# vent_bjt2_i2c_pwm_small.net
KiCad netlist of a schematic drawn in EAGLE
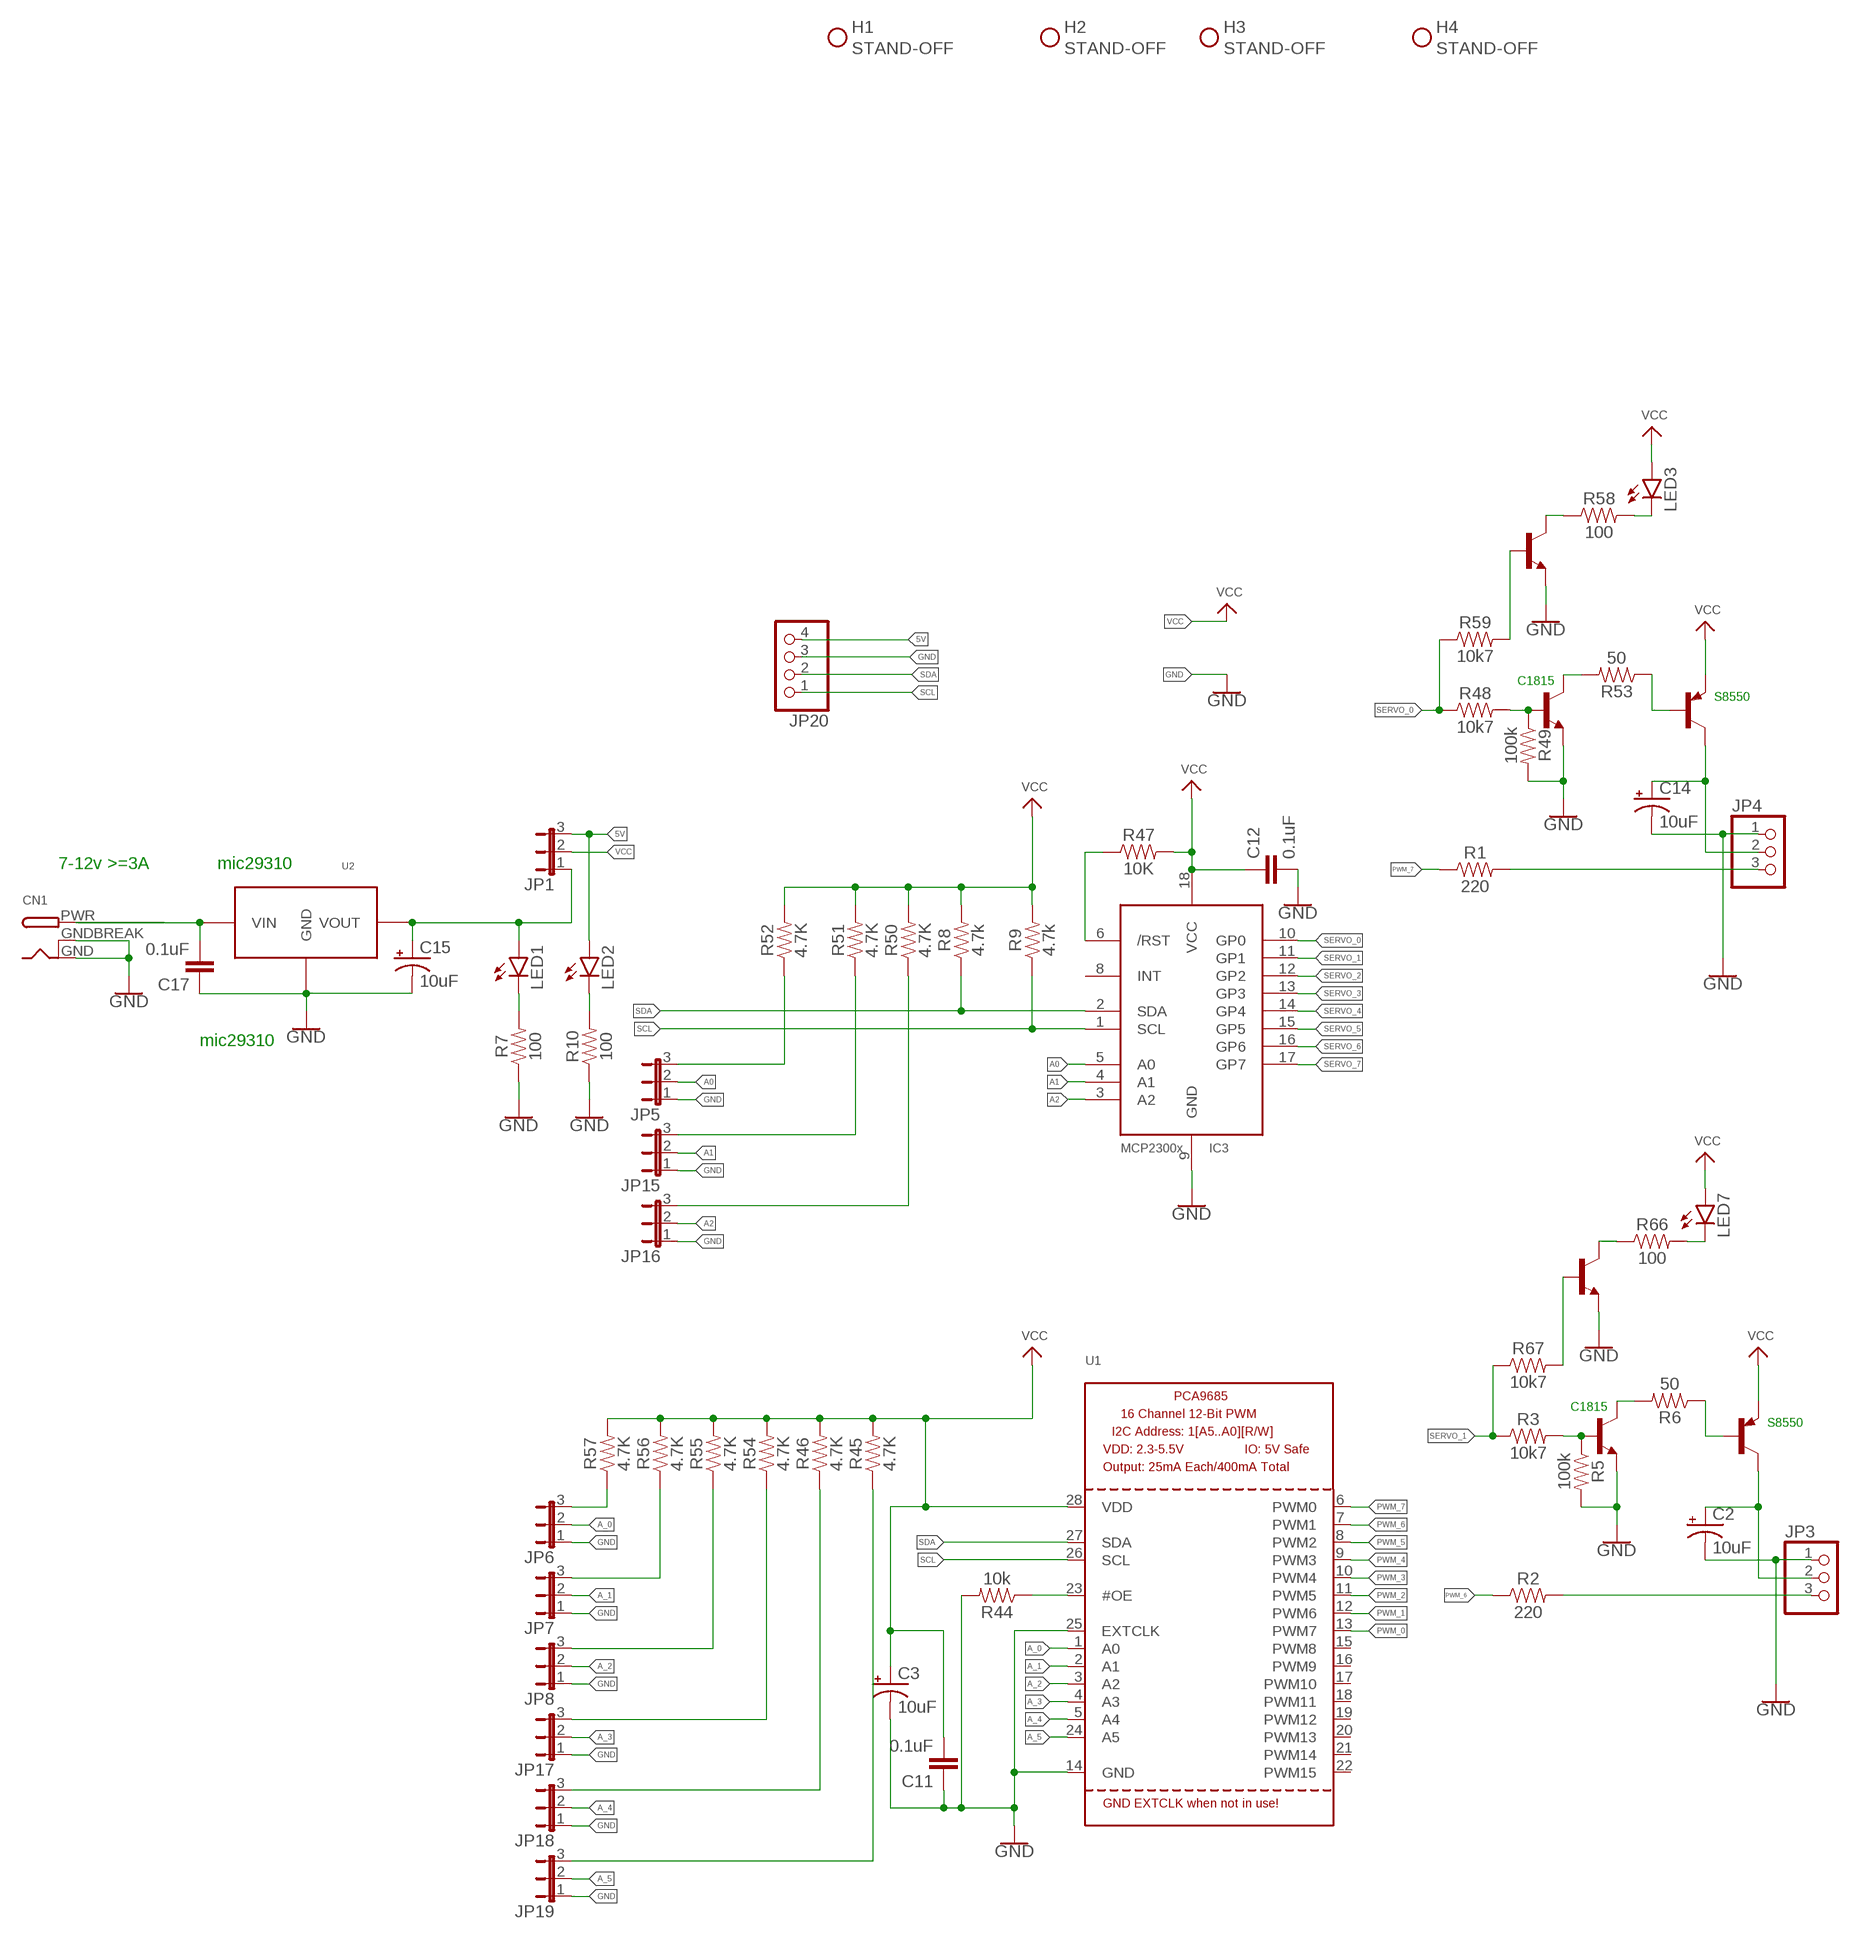
[diagram p0: schematic, sheet 1, part 1 of 2]
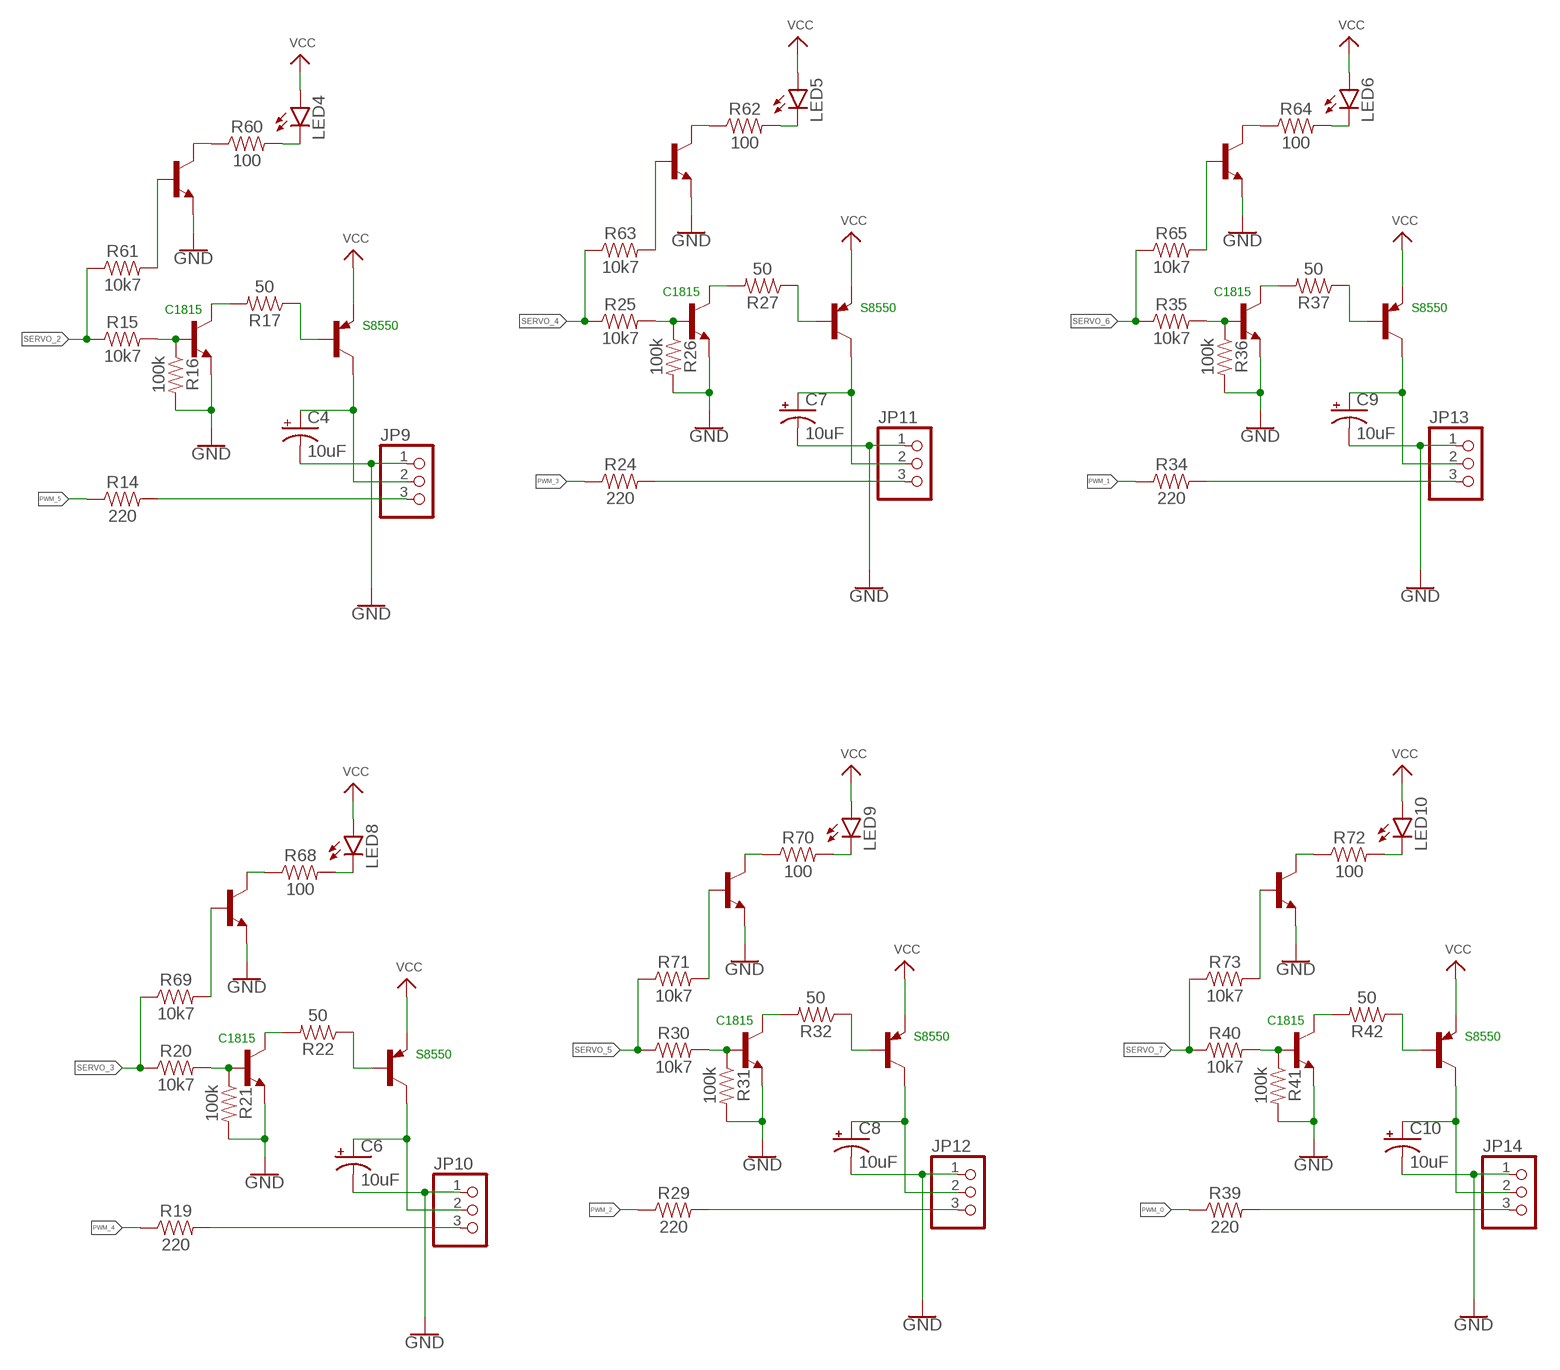
[diagram p1: schematic, sheet 1, part 2 of 2]

(export (version "E")
  (design (tool "Eeschema 10.0.6"))
  (components
    (comp (ref "C2")
      (value "10uF")
      (footprint "eagle-import:CPOL-RADIAL-2.5MM-5MM")
      (libsource (lib "eagle-import") (part "10UF-POLAR-RADIAL-2.5MM-25V-20%"))
    )
    (comp (ref "C3")
      (value "10uF")
      (footprint "eagle-import:CPOL-RADIAL-2.5MM-5MM")
      (libsource (lib "eagle-import") (part "10UF-POLAR-RADIAL-2.5MM-25V-20%"))
    )
    (comp (ref "C4")
      (value "10uF")
      (footprint "eagle-import:CPOL-RADIAL-2.5MM-5MM")
      (libsource (lib "eagle-import") (part "10UF-POLAR-RADIAL-2.5MM-25V-20%"))
    )
    (comp (ref "C6")
      (value "10uF")
      (footprint "eagle-import:CPOL-RADIAL-2.5MM-5MM")
      (libsource (lib "eagle-import") (part "10UF-POLAR-RADIAL-2.5MM-25V-20%"))
    )
    (comp (ref "C7")
      (value "10uF")
      (footprint "eagle-import:CPOL-RADIAL-2.5MM-5MM")
      (libsource (lib "eagle-import") (part "10UF-POLAR-RADIAL-2.5MM-25V-20%"))
    )
    (comp (ref "C8")
      (value "10uF")
      (footprint "eagle-import:CPOL-RADIAL-2.5MM-5MM")
      (libsource (lib "eagle-import") (part "10UF-POLAR-RADIAL-2.5MM-25V-20%"))
    )
    (comp (ref "C9")
      (value "10uF")
      (footprint "eagle-import:CPOL-RADIAL-2.5MM-5MM")
      (libsource (lib "eagle-import") (part "10UF-POLAR-RADIAL-2.5MM-25V-20%"))
    )
    (comp (ref "C10")
      (value "10uF")
      (footprint "eagle-import:CPOL-RADIAL-2.5MM-5MM")
      (libsource (lib "eagle-import") (part "10UF-POLAR-RADIAL-2.5MM-25V-20%"))
    )
    (comp (ref "C11")
      (value "0.1uF")
      (footprint "eagle-import:CAP-PTH-SMALL-KIT")
      (libsource (lib "eagle-import") (part "0.1UF-KIT-EZ-50V-20%"))
    )
    (comp (ref "C12")
      (value "0.1uF")
      (footprint "eagle-import:CAP-PTH-SMALL-KIT")
      (libsource (lib "eagle-import") (part "0.1UF-KIT-EZ-50V-20%"))
    )
    (comp (ref "C14")
      (value "10uF")
      (footprint "eagle-import:CPOL-RADIAL-2.5MM-5MM")
      (libsource (lib "eagle-import") (part "10UF-POLAR-RADIAL-2.5MM-25V-20%"))
    )
    (comp (ref "C15")
      (value "10uF")
      (footprint "eagle-import:CPOL-RADIAL-2.5MM-5MM")
      (libsource (lib "eagle-import") (part "10UF-POLAR-RADIAL-2.5MM-25V-20%"))
    )
    (comp (ref "C17")
      (value "0.1uF")
      (footprint "eagle-import:CAP-PTH-SMALL-KIT")
      (libsource (lib "eagle-import") (part "0.1UF-KIT-EZ-50V-20%"))
    )
    (comp (ref "CN1")
      (value "DCBARRELPTH")
      (footprint "eagle-import:DCJACK_2MM_PTH")
      (libsource (lib "eagle-import") (part "DCBARRELPTH"))
    )
    (comp (ref "H1")
      (value "STAND-OFF")
      (footprint "eagle-import:STAND-OFF")
      (libsource (lib "eagle-import") (part "STAND-OFF"))
    )
    (comp (ref "H2")
      (value "STAND-OFF")
      (footprint "eagle-import:STAND-OFF")
      (libsource (lib "eagle-import") (part "STAND-OFF"))
    )
    (comp (ref "H3")
      (value "STAND-OFF")
      (footprint "eagle-import:STAND-OFF")
      (libsource (lib "eagle-import") (part "STAND-OFF"))
    )
    (comp (ref "H4")
      (value "STAND-OFF")
      (footprint "eagle-import:STAND-OFF")
      (libsource (lib "eagle-import") (part "STAND-OFF"))
    )
    (comp (ref "IC3")
      (value "MCP23008/P")
      (footprint "eagle-import:DIL18")
      (libsource (lib "eagle-import") (part "MCP23008/P"))
    )
    (comp (ref "JP1")
      (value "JP2E")
      (footprint "eagle-import:JP2")
      (libsource (lib "eagle-import") (part "JP2E"))
    )
    (comp (ref "JP3")
      (value "PINHD-1X3")
      (footprint "eagle-import:1X03")
      (libsource (lib "eagle-import") (part "PINHD-1X3"))
    )
    (comp (ref "JP4")
      (value "PINHD-1X3")
      (footprint "eagle-import:1X03")
      (libsource (lib "eagle-import") (part "PINHD-1X3"))
    )
    (comp (ref "JP5")
      (value "JP2E")
      (footprint "eagle-import:JP2")
      (libsource (lib "eagle-import") (part "JP2E"))
    )
    (comp (ref "JP6")
      (value "JP2E")
      (footprint "eagle-import:JP2")
      (libsource (lib "eagle-import") (part "JP2E"))
    )
    (comp (ref "JP7")
      (value "JP2E")
      (footprint "eagle-import:JP2")
      (libsource (lib "eagle-import") (part "JP2E"))
    )
    (comp (ref "JP8")
      (value "JP2E")
      (footprint "eagle-import:JP2")
      (libsource (lib "eagle-import") (part "JP2E"))
    )
    (comp (ref "JP9")
      (value "PINHD-1X3")
      (footprint "eagle-import:1X03")
      (libsource (lib "eagle-import") (part "PINHD-1X3"))
    )
    (comp (ref "JP10")
      (value "PINHD-1X3")
      (footprint "eagle-import:1X03")
      (libsource (lib "eagle-import") (part "PINHD-1X3"))
    )
    (comp (ref "JP11")
      (value "PINHD-1X3")
      (footprint "eagle-import:1X03")
      (libsource (lib "eagle-import") (part "PINHD-1X3"))
    )
    (comp (ref "JP12")
      (value "PINHD-1X3")
      (footprint "eagle-import:1X03")
      (libsource (lib "eagle-import") (part "PINHD-1X3"))
    )
    (comp (ref "JP13")
      (value "PINHD-1X3")
      (footprint "eagle-import:1X03")
      (libsource (lib "eagle-import") (part "PINHD-1X3"))
    )
    (comp (ref "JP14")
      (value "PINHD-1X3")
      (footprint "eagle-import:1X03")
      (libsource (lib "eagle-import") (part "PINHD-1X3"))
    )
    (comp (ref "JP15")
      (value "JP2E")
      (footprint "eagle-import:JP2")
      (libsource (lib "eagle-import") (part "JP2E"))
    )
    (comp (ref "JP16")
      (value "JP2E")
      (footprint "eagle-import:JP2")
      (libsource (lib "eagle-import") (part "JP2E"))
    )
    (comp (ref "JP17")
      (value "JP2E")
      (footprint "eagle-import:JP2")
      (libsource (lib "eagle-import") (part "JP2E"))
    )
    (comp (ref "JP18")
      (value "JP2E")
      (footprint "eagle-import:JP2")
      (libsource (lib "eagle-import") (part "JP2E"))
    )
    (comp (ref "JP19")
      (value "JP2E")
      (footprint "eagle-import:JP2")
      (libsource (lib "eagle-import") (part "JP2E"))
    )
    (comp (ref "JP20")
      (value "PINHD-1X4")
      (footprint "eagle-import:1X04")
      (libsource (lib "eagle-import") (part "PINHD-1X4"))
    )
    (comp (ref "LED1")
      (value "LEDCHIPLED_1206")
      (footprint "eagle-import:CHIPLED_1206")
      (libsource (lib "eagle-import") (part "LEDCHIPLED_1206"))
    )
    (comp (ref "LED2")
      (value "LEDCHIPLED_1206")
      (footprint "eagle-import:CHIPLED_1206")
      (libsource (lib "eagle-import") (part "LEDCHIPLED_1206"))
    )
    (comp (ref "LED3")
      (value "LEDCHIPLED_1206")
      (footprint "eagle-import:CHIPLED_1206")
      (libsource (lib "eagle-import") (part "LEDCHIPLED_1206"))
    )
    (comp (ref "LED4")
      (value "LEDCHIPLED_1206")
      (footprint "eagle-import:CHIPLED_1206")
      (libsource (lib "eagle-import") (part "LEDCHIPLED_1206"))
    )
    (comp (ref "LED5")
      (value "LEDCHIPLED_1206")
      (footprint "eagle-import:CHIPLED_1206")
      (libsource (lib "eagle-import") (part "LEDCHIPLED_1206"))
    )
    (comp (ref "LED6")
      (value "LEDCHIPLED_1206")
      (footprint "eagle-import:CHIPLED_1206")
      (libsource (lib "eagle-import") (part "LEDCHIPLED_1206"))
    )
    (comp (ref "LED7")
      (value "LEDCHIPLED_1206")
      (footprint "eagle-import:CHIPLED_1206")
      (libsource (lib "eagle-import") (part "LEDCHIPLED_1206"))
    )
    (comp (ref "LED8")
      (value "LEDCHIPLED_1206")
      (footprint "eagle-import:CHIPLED_1206")
      (libsource (lib "eagle-import") (part "LEDCHIPLED_1206"))
    )
    (comp (ref "LED9")
      (value "LEDCHIPLED_1206")
      (footprint "eagle-import:CHIPLED_1206")
      (libsource (lib "eagle-import") (part "LEDCHIPLED_1206"))
    )
    (comp (ref "LED10")
      (value "LEDCHIPLED_1206")
      (footprint "eagle-import:CHIPLED_1206")
      (libsource (lib "eagle-import") (part "LEDCHIPLED_1206"))
    )
    (comp (ref "Q1")
      (value "2N2907")
      (footprint "eagle-import:TO92-EBC-OVAL")
      (libsource (lib "eagle-import") (part "2N2907"))
    )
    (comp (ref "Q2")
      (value "2N2907")
      (footprint "eagle-import:TO92-EBC-OVAL")
      (libsource (lib "eagle-import") (part "2N2907"))
    )
    (comp (ref "Q3")
      (value "2N2907")
      (footprint "eagle-import:TO92-EBC-OVAL")
      (libsource (lib "eagle-import") (part "2N2907"))
    )
    (comp (ref "Q4")
      (value "2N2907")
      (footprint "eagle-import:TO92-EBC-OVAL")
      (libsource (lib "eagle-import") (part "2N2907"))
    )
    (comp (ref "Q5")
      (value "2N2907")
      (footprint "eagle-import:TO92-EBC-OVAL")
      (libsource (lib "eagle-import") (part "2N2907"))
    )
    (comp (ref "Q6")
      (value "2N2907")
      (footprint "eagle-import:TO92-EBC-OVAL")
      (libsource (lib "eagle-import") (part "2N2907"))
    )
    (comp (ref "Q7")
      (value "2N2907")
      (footprint "eagle-import:TO92-EBC-OVAL")
      (libsource (lib "eagle-import") (part "2N2907"))
    )
    (comp (ref "Q9")
      (value "2N2907")
      (footprint "eagle-import:TO92-EBC-OVAL")
      (libsource (lib "eagle-import") (part "2N2907"))
    )
    (comp (ref "R1")
      (value "220")
      (footprint "eagle-import:AXIAL-0.3")
      (libsource (lib "eagle-import") (part "10KOHM-HORIZ-1/4W-1%"))
    )
    (comp (ref "R2")
      (value "220")
      (footprint "eagle-import:AXIAL-0.3")
      (libsource (lib "eagle-import") (part "10KOHM-HORIZ-1/4W-1%"))
    )
    (comp (ref "R3")
      (value "10k7")
      (footprint "eagle-import:AXIAL-0.3")
      (libsource (lib "eagle-import") (part "10KOHM-HORIZ-1/4W-1%"))
    )
    (comp (ref "R5")
      (value "100k")
      (footprint "eagle-import:AXIAL-0.3")
      (libsource (lib "eagle-import") (part "10KOHM-HORIZ-1/4W-1%"))
    )
    (comp (ref "R6")
      (value "50")
      (footprint "eagle-import:AXIAL-0.3")
      (libsource (lib "eagle-import") (part "10KOHM-HORIZ-1/4W-1%"))
    )
    (comp (ref "R7")
      (value "100")
      (footprint "eagle-import:AXIAL-0.3")
      (libsource (lib "eagle-import") (part "10KOHM-HORIZ-1/4W-1%"))
    )
    (comp (ref "R8")
      (value "4.7k")
      (footprint "eagle-import:AXIAL-0.3")
      (libsource (lib "eagle-import") (part "10KOHM-HORIZ-1/4W-1%"))
    )
    (comp (ref "R9")
      (value "4.7k")
      (footprint "eagle-import:AXIAL-0.3")
      (libsource (lib "eagle-import") (part "10KOHM-HORIZ-1/4W-1%"))
    )
    (comp (ref "R10")
      (value "100")
      (footprint "eagle-import:AXIAL-0.3")
      (libsource (lib "eagle-import") (part "10KOHM-HORIZ-1/4W-1%"))
    )
    (comp (ref "R14")
      (value "220")
      (footprint "eagle-import:AXIAL-0.3")
      (libsource (lib "eagle-import") (part "10KOHM-HORIZ-1/4W-1%"))
    )
    (comp (ref "R15")
      (value "10k7")
      (footprint "eagle-import:AXIAL-0.3")
      (libsource (lib "eagle-import") (part "10KOHM-HORIZ-1/4W-1%"))
    )
    (comp (ref "R16")
      (value "100k")
      (footprint "eagle-import:AXIAL-0.3")
      (libsource (lib "eagle-import") (part "10KOHM-HORIZ-1/4W-1%"))
    )
    (comp (ref "R17")
      (value "50")
      (footprint "eagle-import:AXIAL-0.3")
      (libsource (lib "eagle-import") (part "10KOHM-HORIZ-1/4W-1%"))
    )
    (comp (ref "R19")
      (value "220")
      (footprint "eagle-import:AXIAL-0.3")
      (libsource (lib "eagle-import") (part "10KOHM-HORIZ-1/4W-1%"))
    )
    (comp (ref "R20")
      (value "10k7")
      (footprint "eagle-import:AXIAL-0.3")
      (libsource (lib "eagle-import") (part "10KOHM-HORIZ-1/4W-1%"))
    )
    (comp (ref "R21")
      (value "100k")
      (footprint "eagle-import:AXIAL-0.3")
      (libsource (lib "eagle-import") (part "10KOHM-HORIZ-1/4W-1%"))
    )
    (comp (ref "R22")
      (value "50")
      (footprint "eagle-import:AXIAL-0.3")
      (libsource (lib "eagle-import") (part "10KOHM-HORIZ-1/4W-1%"))
    )
    (comp (ref "R24")
      (value "220")
      (footprint "eagle-import:AXIAL-0.3")
      (libsource (lib "eagle-import") (part "10KOHM-HORIZ-1/4W-1%"))
    )
    (comp (ref "R25")
      (value "10k7")
      (footprint "eagle-import:AXIAL-0.3")
      (libsource (lib "eagle-import") (part "10KOHM-HORIZ-1/4W-1%"))
    )
    (comp (ref "R26")
      (value "100k")
      (footprint "eagle-import:AXIAL-0.3")
      (libsource (lib "eagle-import") (part "10KOHM-HORIZ-1/4W-1%"))
    )
    (comp (ref "R27")
      (value "50")
      (footprint "eagle-import:AXIAL-0.3")
      (libsource (lib "eagle-import") (part "10KOHM-HORIZ-1/4W-1%"))
    )
    (comp (ref "R29")
      (value "220")
      (footprint "eagle-import:AXIAL-0.3")
      (libsource (lib "eagle-import") (part "10KOHM-HORIZ-1/4W-1%"))
    )
    (comp (ref "R30")
      (value "10k7")
      (footprint "eagle-import:AXIAL-0.3")
      (libsource (lib "eagle-import") (part "10KOHM-HORIZ-1/4W-1%"))
    )
    (comp (ref "R31")
      (value "100k")
      (footprint "eagle-import:AXIAL-0.3")
      (libsource (lib "eagle-import") (part "10KOHM-HORIZ-1/4W-1%"))
    )
    (comp (ref "R32")
      (value "50")
      (footprint "eagle-import:AXIAL-0.3")
      (libsource (lib "eagle-import") (part "10KOHM-HORIZ-1/4W-1%"))
    )
    (comp (ref "R34")
      (value "220")
      (footprint "eagle-import:AXIAL-0.3")
      (libsource (lib "eagle-import") (part "10KOHM-HORIZ-1/4W-1%"))
    )
    (comp (ref "R35")
      (value "10k7")
      (footprint "eagle-import:AXIAL-0.3")
      (libsource (lib "eagle-import") (part "10KOHM-HORIZ-1/4W-1%"))
    )
    (comp (ref "R36")
      (value "100k")
      (footprint "eagle-import:AXIAL-0.3")
      (libsource (lib "eagle-import") (part "10KOHM-HORIZ-1/4W-1%"))
    )
    (comp (ref "R37")
      (value "50")
      (footprint "eagle-import:AXIAL-0.3")
      (libsource (lib "eagle-import") (part "10KOHM-HORIZ-1/4W-1%"))
    )
    (comp (ref "R39")
      (value "220")
      (footprint "eagle-import:AXIAL-0.3")
      (libsource (lib "eagle-import") (part "10KOHM-HORIZ-1/4W-1%"))
    )
    (comp (ref "R40")
      (value "10k7")
      (footprint "eagle-import:AXIAL-0.3")
      (libsource (lib "eagle-import") (part "10KOHM-HORIZ-1/4W-1%"))
    )
    (comp (ref "R41")
      (value "100k")
      (footprint "eagle-import:AXIAL-0.3")
      (libsource (lib "eagle-import") (part "10KOHM-HORIZ-1/4W-1%"))
    )
    (comp (ref "R42")
      (value "50")
      (footprint "eagle-import:AXIAL-0.3")
      (libsource (lib "eagle-import") (part "10KOHM-HORIZ-1/4W-1%"))
    )
    (comp (ref "R44")
      (value "10k")
      (footprint "eagle-import:AXIAL-0.3")
      (libsource (lib "eagle-import") (part "10KOHM-HORIZ-1/4W-1%"))
    )
    (comp (ref "R45")
      (value "4.7K")
      (footprint "eagle-import:AXIAL-0.3")
      (libsource (lib "eagle-import") (part "10KOHM-HORIZ-1/4W-1%"))
    )
    (comp (ref "R46")
      (value "4.7K")
      (footprint "eagle-import:AXIAL-0.3")
      (libsource (lib "eagle-import") (part "10KOHM-HORIZ-1/4W-1%"))
    )
    (comp (ref "R47")
      (value "10K")
      (footprint "eagle-import:AXIAL-0.3")
      (libsource (lib "eagle-import") (part "10KOHM-HORIZ-1/4W-1%"))
    )
    (comp (ref "R48")
      (value "10k7")
      (footprint "eagle-import:AXIAL-0.3")
      (libsource (lib "eagle-import") (part "10KOHM-HORIZ-1/4W-1%"))
    )
    (comp (ref "R49")
      (value "100k")
      (footprint "eagle-import:AXIAL-0.3")
      (libsource (lib "eagle-import") (part "10KOHM-HORIZ-1/4W-1%"))
    )
    (comp (ref "R50")
      (value "4.7K")
      (footprint "eagle-import:AXIAL-0.3")
      (libsource (lib "eagle-import") (part "10KOHM-HORIZ-1/4W-1%"))
    )
    (comp (ref "R51")
      (value "4.7K")
      (footprint "eagle-import:AXIAL-0.3")
      (libsource (lib "eagle-import") (part "10KOHM-HORIZ-1/4W-1%"))
    )
    (comp (ref "R52")
      (value "4.7K")
      (footprint "eagle-import:AXIAL-0.3")
      (libsource (lib "eagle-import") (part "10KOHM-HORIZ-1/4W-1%"))
    )
    (comp (ref "R53")
      (value "50")
      (footprint "eagle-import:AXIAL-0.3")
      (libsource (lib "eagle-import") (part "10KOHM-HORIZ-1/4W-1%"))
    )
    (comp (ref "R54")
      (value "4.7K")
      (footprint "eagle-import:AXIAL-0.3")
      (libsource (lib "eagle-import") (part "10KOHM-HORIZ-1/4W-1%"))
    )
    (comp (ref "R55")
      (value "4.7K")
      (footprint "eagle-import:AXIAL-0.3")
      (libsource (lib "eagle-import") (part "10KOHM-HORIZ-1/4W-1%"))
    )
    (comp (ref "R56")
      (value "4.7K")
      (footprint "eagle-import:AXIAL-0.3")
      (libsource (lib "eagle-import") (part "10KOHM-HORIZ-1/4W-1%"))
    )
    (comp (ref "R57")
      (value "4.7K")
      (footprint "eagle-import:AXIAL-0.3")
      (libsource (lib "eagle-import") (part "10KOHM-HORIZ-1/4W-1%"))
    )
    (comp (ref "R58")
      (value "100")
      (footprint "eagle-import:AXIAL-0.3")
      (libsource (lib "eagle-import") (part "10KOHM-HORIZ-1/4W-1%"))
    )
    (comp (ref "R59")
      (value "10k7")
      (footprint "eagle-import:AXIAL-0.3")
      (libsource (lib "eagle-import") (part "10KOHM-HORIZ-1/4W-1%"))
    )
    (comp (ref "R60")
      (value "100")
      (footprint "eagle-import:AXIAL-0.3")
      (libsource (lib "eagle-import") (part "10KOHM-HORIZ-1/4W-1%"))
    )
    (comp (ref "R61")
      (value "10k7")
      (footprint "eagle-import:AXIAL-0.3")
      (libsource (lib "eagle-import") (part "10KOHM-HORIZ-1/4W-1%"))
    )
    (comp (ref "R62")
      (value "100")
      (footprint "eagle-import:AXIAL-0.3")
      (libsource (lib "eagle-import") (part "10KOHM-HORIZ-1/4W-1%"))
    )
    (comp (ref "R63")
      (value "10k7")
      (footprint "eagle-import:AXIAL-0.3")
      (libsource (lib "eagle-import") (part "10KOHM-HORIZ-1/4W-1%"))
    )
    (comp (ref "R64")
      (value "100")
      (footprint "eagle-import:AXIAL-0.3")
      (libsource (lib "eagle-import") (part "10KOHM-HORIZ-1/4W-1%"))
    )
    (comp (ref "R65")
      (value "10k7")
      (footprint "eagle-import:AXIAL-0.3")
      (libsource (lib "eagle-import") (part "10KOHM-HORIZ-1/4W-1%"))
    )
    (comp (ref "R66")
      (value "100")
      (footprint "eagle-import:AXIAL-0.3")
      (libsource (lib "eagle-import") (part "10KOHM-HORIZ-1/4W-1%"))
    )
    (comp (ref "R67")
      (value "10k7")
      (footprint "eagle-import:AXIAL-0.3")
      (libsource (lib "eagle-import") (part "10KOHM-HORIZ-1/4W-1%"))
    )
    (comp (ref "R68")
      (value "100")
      (footprint "eagle-import:AXIAL-0.3")
      (libsource (lib "eagle-import") (part "10KOHM-HORIZ-1/4W-1%"))
    )
    (comp (ref "R69")
      (value "10k7")
      (footprint "eagle-import:AXIAL-0.3")
      (libsource (lib "eagle-import") (part "10KOHM-HORIZ-1/4W-1%"))
    )
    (comp (ref "R70")
      (value "100")
      (footprint "eagle-import:AXIAL-0.3")
      (libsource (lib "eagle-import") (part "10KOHM-HORIZ-1/4W-1%"))
    )
    (comp (ref "R71")
      (value "10k7")
      (footprint "eagle-import:AXIAL-0.3")
      (libsource (lib "eagle-import") (part "10KOHM-HORIZ-1/4W-1%"))
    )
    (comp (ref "R72")
      (value "100")
      (footprint "eagle-import:AXIAL-0.3")
      (libsource (lib "eagle-import") (part "10KOHM-HORIZ-1/4W-1%"))
    )
    (comp (ref "R73")
      (value "10k7")
      (footprint "eagle-import:AXIAL-0.3")
      (libsource (lib "eagle-import") (part "10KOHM-HORIZ-1/4W-1%"))
    )
    (comp (ref "T1")
      (value "2SC1815")
      (footprint "eagle-import:TO92-ECB")
      (libsource (lib "eagle-import") (part "2SC1815"))
    )
    (comp (ref "T2")
      (value "2SC1815")
      (footprint "eagle-import:TO92-ECB")
      (libsource (lib "eagle-import") (part "2SC1815"))
    )
    (comp (ref "T3")
      (value "2SC1815")
      (footprint "eagle-import:TO92-ECB")
      (libsource (lib "eagle-import") (part "2SC1815"))
    )
    (comp (ref "T4")
      (value "2SC1815")
      (footprint "eagle-import:TO92-ECB")
      (libsource (lib "eagle-import") (part "2SC1815"))
    )
    (comp (ref "T5")
      (value "2SC1815")
      (footprint "eagle-import:TO92-ECB")
      (libsource (lib "eagle-import") (part "2SC1815"))
    )
    (comp (ref "T6")
      (value "2SC1815")
      (footprint "eagle-import:TO92-ECB")
      (libsource (lib "eagle-import") (part "2SC1815"))
    )
    (comp (ref "T7")
      (value "2SC1815")
      (footprint "eagle-import:TO92-ECB")
      (libsource (lib "eagle-import") (part "2SC1815"))
    )
    (comp (ref "T9")
      (value "2SC1815")
      (footprint "eagle-import:TO92-ECB")
      (libsource (lib "eagle-import") (part "2SC1815"))
    )
    (comp (ref "U1")
      (value "PCA9685")
      (footprint "eagle-import:TSSOP28")
      (libsource (lib "eagle-import") (part "PCA9685"))
    )
    (comp (ref "U2")
      (value "MIC29310_TO-263")
      (footprint "eagle-import:TO263-3")
      (libsource (lib "eagle-import") (part "MIC29310_TO-263"))
    )
    (comp (ref "U3")
      (value "S9018")
      (footprint "eagle-import:TO92-EBC")
      (libsource (lib "eagle-import") (part "S9018"))
    )
    (comp (ref "U4")
      (value "S9018")
      (footprint "eagle-import:TO92-EBC")
      (libsource (lib "eagle-import") (part "S9018"))
    )
    (comp (ref "U5")
      (value "S9018")
      (footprint "eagle-import:TO92-EBC")
      (libsource (lib "eagle-import") (part "S9018"))
    )
    (comp (ref "U6")
      (value "S9018")
      (footprint "eagle-import:TO92-EBC")
      (libsource (lib "eagle-import") (part "S9018"))
    )
    (comp (ref "U7")
      (value "S9018")
      (footprint "eagle-import:TO92-EBC")
      (libsource (lib "eagle-import") (part "S9018"))
    )
    (comp (ref "U8")
      (value "S9018")
      (footprint "eagle-import:TO92-EBC")
      (libsource (lib "eagle-import") (part "S9018"))
    )
    (comp (ref "U9")
      (value "S9018")
      (footprint "eagle-import:TO92-EBC")
      (libsource (lib "eagle-import") (part "S9018"))
    )
    (comp (ref "U10")
      (value "S9018")
      (footprint "eagle-import:TO92-EBC")
      (libsource (lib "eagle-import") (part "S9018"))
    )
  )
  (nets
    (net (code "1") (name "5V") (class "Default")
      (node (ref "JP1") (pin "3") (pinfunction "3_3") (pintype "passive"))
      (node (ref "JP20") (pin "4") (pinfunction "4_4") (pintype "passive"))
      (node (ref "LED2") (pin "A") (pinfunction "A_A") (pintype "passive"))
    )
    (net (code "2") (name "A0") (class "Default")
      (node (ref "IC3") (pin "5") (pinfunction "A0_5") (pintype "input"))
      (node (ref "JP5") (pin "2") (pinfunction "2_2") (pintype "passive"))
    )
    (net (code "3") (name "A1") (class "Default")
      (node (ref "IC3") (pin "4") (pinfunction "A1_4") (pintype "input"))
      (node (ref "JP15") (pin "2") (pinfunction "2_2") (pintype "passive"))
    )
    (net (code "4") (name "A2") (class "Default")
      (node (ref "IC3") (pin "3") (pinfunction "A2_3") (pintype "input"))
      (node (ref "JP16") (pin "2") (pinfunction "2_2") (pintype "passive"))
    )
    (net (code "5") (name "A_0") (class "Default")
      (node (ref "JP6") (pin "2") (pinfunction "2_2") (pintype "passive"))
      (node (ref "U1") (pin "1") (pinfunction "A0_1") (pintype "bidirectional"))
    )
    (net (code "6") (name "A_1") (class "Default")
      (node (ref "JP7") (pin "2") (pinfunction "2_2") (pintype "passive"))
      (node (ref "U1") (pin "2") (pinfunction "A1_2") (pintype "bidirectional"))
    )
    (net (code "7") (name "A_2") (class "Default")
      (node (ref "JP8") (pin "2") (pinfunction "2_2") (pintype "passive"))
      (node (ref "U1") (pin "3") (pinfunction "A2_3") (pintype "bidirectional"))
    )
    (net (code "8") (name "A_3") (class "Default")
      (node (ref "JP17") (pin "2") (pinfunction "2_2") (pintype "passive"))
      (node (ref "U1") (pin "4") (pinfunction "A3_4") (pintype "bidirectional"))
    )
    (net (code "9") (name "A_4") (class "Default")
      (node (ref "JP18") (pin "2") (pinfunction "2_2") (pintype "passive"))
      (node (ref "U1") (pin "5") (pinfunction "A4_5") (pintype "bidirectional"))
    )
    (net (code "10") (name "A_5") (class "Default")
      (node (ref "JP19") (pin "2") (pinfunction "2_2") (pintype "passive"))
      (node (ref "U1") (pin "24") (pinfunction "A5_24") (pintype "bidirectional"))
    )
    (net (code "11") (name "GND") (class "Default")
      (node (ref "C10") (pin "2") (pinfunction "-_2") (pintype "passive"))
      (node (ref "C11") (pin "1") (pinfunction "1_1") (pintype "passive"))
      (node (ref "C12") (pin "2") (pinfunction "2_2") (pintype "passive"))
      (node (ref "C14") (pin "2") (pinfunction "-_2") (pintype "passive"))
      (node (ref "C15") (pin "2") (pinfunction "-_2") (pintype "passive"))
      (node (ref "C17") (pin "1") (pinfunction "1_1") (pintype "passive"))
      (node (ref "C2") (pin "2") (pinfunction "-_2") (pintype "passive"))
      (node (ref "C3") (pin "2") (pinfunction "-_2") (pintype "passive"))
      (node (ref "C4") (pin "2") (pinfunction "-_2") (pintype "passive"))
      (node (ref "C6") (pin "2") (pinfunction "-_2") (pintype "passive"))
      (node (ref "C7") (pin "2") (pinfunction "-_2") (pintype "passive"))
      (node (ref "C8") (pin "2") (pinfunction "-_2") (pintype "passive"))
      (node (ref "C9") (pin "2") (pinfunction "-_2") (pintype "passive"))
      (node (ref "CN1") (pin "GND") (pinfunction "GND_GND") (pintype "power_in"))
      (node (ref "CN1") (pin "GNDBREAK") (pinfunction "GNDBREAK_GNDBREAK") (pintype "power_in"))
      (node (ref "IC3") (pin "9") (pinfunction "GND_9") (pintype "power_in"))
      (node (ref "JP10") (pin "1") (pinfunction "1_1") (pintype "passive"))
      (node (ref "JP11") (pin "1") (pinfunction "1_1") (pintype "passive"))
      (node (ref "JP12") (pin "1") (pinfunction "1_1") (pintype "passive"))
      (node (ref "JP13") (pin "1") (pinfunction "1_1") (pintype "passive"))
      (node (ref "JP14") (pin "1") (pinfunction "1_1") (pintype "passive"))
      (node (ref "JP15") (pin "1") (pinfunction "1_1") (pintype "passive"))
      (node (ref "JP16") (pin "1") (pinfunction "1_1") (pintype "passive"))
      (node (ref "JP17") (pin "1") (pinfunction "1_1") (pintype "passive"))
      (node (ref "JP18") (pin "1") (pinfunction "1_1") (pintype "passive"))
      (node (ref "JP19") (pin "1") (pinfunction "1_1") (pintype "passive"))
      (node (ref "JP20") (pin "3") (pinfunction "3_3") (pintype "passive"))
      (node (ref "JP3") (pin "1") (pinfunction "1_1") (pintype "passive"))
      (node (ref "JP4") (pin "1") (pinfunction "1_1") (pintype "passive"))
      (node (ref "JP5") (pin "1") (pinfunction "1_1") (pintype "passive"))
      (node (ref "JP6") (pin "1") (pinfunction "1_1") (pintype "passive"))
      (node (ref "JP7") (pin "1") (pinfunction "1_1") (pintype "passive"))
      (node (ref "JP8") (pin "1") (pinfunction "1_1") (pintype "passive"))
      (node (ref "JP9") (pin "1") (pinfunction "1_1") (pintype "passive"))
      (node (ref "R10") (pin "P$1") (pinfunction "1_P$1") (pintype "passive"))
      (node (ref "R16") (pin "P$2") (pinfunction "2_P$2") (pintype "passive"))
      (node (ref "R21") (pin "P$2") (pinfunction "2_P$2") (pintype "passive"))
      (node (ref "R26") (pin "P$2") (pinfunction "2_P$2") (pintype "passive"))
      (node (ref "R31") (pin "P$2") (pinfunction "2_P$2") (pintype "passive"))
      (node (ref "R36") (pin "P$2") (pinfunction "2_P$2") (pintype "passive"))
      (node (ref "R41") (pin "P$2") (pinfunction "2_P$2") (pintype "passive"))
      (node (ref "R44") (pin "P$2") (pinfunction "2_P$2") (pintype "passive"))
      (node (ref "R49") (pin "P$2") (pinfunction "2_P$2") (pintype "passive"))
      (node (ref "R5") (pin "P$2") (pinfunction "2_P$2") (pintype "passive"))
      (node (ref "R7") (pin "P$1") (pinfunction "1_P$1") (pintype "passive"))
      (node (ref "T1") (pin "E") (pinfunction "E_E") (pintype "passive"))
      (node (ref "T2") (pin "E") (pinfunction "E_E") (pintype "passive"))
      (node (ref "T3") (pin "E") (pinfunction "E_E") (pintype "passive"))
      (node (ref "T4") (pin "E") (pinfunction "E_E") (pintype "passive"))
      (node (ref "T5") (pin "E") (pinfunction "E_E") (pintype "passive"))
      (node (ref "T6") (pin "E") (pinfunction "E_E") (pintype "passive"))
      (node (ref "T7") (pin "E") (pinfunction "E_E") (pintype "passive"))
      (node (ref "T9") (pin "E") (pinfunction "E_E") (pintype "passive"))
      (node (ref "U1") (pin "14") (pinfunction "GND_14") (pintype "power_in"))
      (node (ref "U1") (pin "25") (pinfunction "EXTCLK_25") (pintype "input"))
      (node (ref "U10") (pin "E") (pinfunction "E_E") (pintype "passive"))
      (node (ref "U2") (pin "2") (pinfunction "GND_2") (pintype "power_in"))
      (node (ref "U2") (pin "TAB") (pinfunction "GND_TAB") (pintype "power_in"))
      (node (ref "U3") (pin "E") (pinfunction "E_E") (pintype "passive"))
      (node (ref "U4") (pin "E") (pinfunction "E_E") (pintype "passive"))
      (node (ref "U5") (pin "E") (pinfunction "E_E") (pintype "passive"))
      (node (ref "U6") (pin "E") (pinfunction "E_E") (pintype "passive"))
      (node (ref "U7") (pin "E") (pinfunction "E_E") (pintype "passive"))
      (node (ref "U8") (pin "E") (pinfunction "E_E") (pintype "passive"))
      (node (ref "U9") (pin "E") (pinfunction "E_E") (pintype "passive"))
    )
    (net (code "12") (name "Net-(C2-+)") (class "Default")
      (node (ref "C2") (pin "1") (pinfunction "+_1") (pintype "passive"))
      (node (ref "JP3") (pin "2") (pinfunction "2_2") (pintype "passive"))
      (node (ref "Q1") (pin "C") (pinfunction "C_C") (pintype "passive"))
    )
    (net (code "13") (name "Net-(C4-+)") (class "Default")
      (node (ref "C4") (pin "1") (pinfunction "+_1") (pintype "passive"))
      (node (ref "JP9") (pin "2") (pinfunction "2_2") (pintype "passive"))
      (node (ref "Q2") (pin "C") (pinfunction "C_C") (pintype "passive"))
    )
    (net (code "14") (name "Net-(C6-+)") (class "Default")
      (node (ref "C6") (pin "1") (pinfunction "+_1") (pintype "passive"))
      (node (ref "JP10") (pin "2") (pinfunction "2_2") (pintype "passive"))
      (node (ref "Q3") (pin "C") (pinfunction "C_C") (pintype "passive"))
    )
    (net (code "15") (name "Net-(C7-+)") (class "Default")
      (node (ref "C7") (pin "1") (pinfunction "+_1") (pintype "passive"))
      (node (ref "JP11") (pin "2") (pinfunction "2_2") (pintype "passive"))
      (node (ref "Q4") (pin "C") (pinfunction "C_C") (pintype "passive"))
    )
    (net (code "16") (name "Net-(C8-+)") (class "Default")
      (node (ref "C8") (pin "1") (pinfunction "+_1") (pintype "passive"))
      (node (ref "JP12") (pin "2") (pinfunction "2_2") (pintype "passive"))
      (node (ref "Q5") (pin "C") (pinfunction "C_C") (pintype "passive"))
    )
    (net (code "17") (name "Net-(C9-+)") (class "Default")
      (node (ref "C9") (pin "1") (pinfunction "+_1") (pintype "passive"))
      (node (ref "JP13") (pin "2") (pinfunction "2_2") (pintype "passive"))
      (node (ref "Q6") (pin "C") (pinfunction "C_C") (pintype "passive"))
    )
    (net (code "18") (name "Net-(C10-+)") (class "Default")
      (node (ref "C10") (pin "1") (pinfunction "+_1") (pintype "passive"))
      (node (ref "JP14") (pin "2") (pinfunction "2_2") (pintype "passive"))
      (node (ref "Q7") (pin "C") (pinfunction "C_C") (pintype "passive"))
    )
    (net (code "19") (name "Net-(C14-+)") (class "Default")
      (node (ref "C14") (pin "1") (pinfunction "+_1") (pintype "passive"))
      (node (ref "JP4") (pin "2") (pinfunction "2_2") (pintype "passive"))
      (node (ref "Q9") (pin "C") (pinfunction "C_C") (pintype "passive"))
    )
    (net (code "20") (name "Net-(C15-+)") (class "Default")
      (node (ref "C15") (pin "1") (pinfunction "+_1") (pintype "passive"))
      (node (ref "JP1") (pin "1") (pinfunction "1_1") (pintype "passive"))
      (node (ref "LED1") (pin "A") (pinfunction "A_A") (pintype "passive"))
      (node (ref "U2") (pin "3") (pinfunction "VOUT_3") (pintype "power_in"))
    )
    (net (code "21") (name "Net-(IC3-{slash}RST)") (class "Default")
      (node (ref "IC3") (pin "6") (pinfunction "/RST_6") (pintype "input"))
      (node (ref "R47") (pin "P$1") (pinfunction "1_P$1") (pintype "passive"))
    )
    (net (code "22") (name "Net-(R1-2)") (class "Default")
      (node (ref "JP4") (pin "3") (pinfunction "3_3") (pintype "passive"))
      (node (ref "R1") (pin "P$2") (pinfunction "2_P$2") (pintype "passive"))
    )
    (net (code "23") (name "Net-(R2-2)") (class "Default")
      (node (ref "JP3") (pin "3") (pinfunction "3_3") (pintype "passive"))
      (node (ref "R2") (pin "P$2") (pinfunction "2_P$2") (pintype "passive"))
    )
    (net (code "24") (name "Net-(R3-2)") (class "Default")
      (node (ref "R3") (pin "P$2") (pinfunction "2_P$2") (pintype "passive"))
      (node (ref "R5") (pin "P$1") (pinfunction "1_P$1") (pintype "passive"))
      (node (ref "T1") (pin "B") (pinfunction "B_B") (pintype "passive"))
    )
    (net (code "25") (name "Net-(R6-1)") (class "Default")
      (node (ref "Q1") (pin "B") (pinfunction "B_B") (pintype "passive"))
      (node (ref "R6") (pin "P$1") (pinfunction "1_P$1") (pintype "passive"))
    )
    (net (code "26") (name "Net-(R6-2)") (class "Default")
      (node (ref "R6") (pin "P$2") (pinfunction "2_P$2") (pintype "passive"))
      (node (ref "T1") (pin "C") (pinfunction "C_C") (pintype "passive"))
    )
    (net (code "27") (name "Net-(R7-2)") (class "Default")
      (node (ref "LED1") (pin "C") (pinfunction "C_C") (pintype "passive"))
      (node (ref "R7") (pin "P$2") (pinfunction "2_P$2") (pintype "passive"))
    )
    (net (code "28") (name "Net-(R10-2)") (class "Default")
      (node (ref "LED2") (pin "C") (pinfunction "C_C") (pintype "passive"))
      (node (ref "R10") (pin "P$2") (pinfunction "2_P$2") (pintype "passive"))
    )
    (net (code "29") (name "Net-(R14-2)") (class "Default")
      (node (ref "JP9") (pin "3") (pinfunction "3_3") (pintype "passive"))
      (node (ref "R14") (pin "P$2") (pinfunction "2_P$2") (pintype "passive"))
    )
    (net (code "30") (name "Net-(R15-2)") (class "Default")
      (node (ref "R15") (pin "P$2") (pinfunction "2_P$2") (pintype "passive"))
      (node (ref "R16") (pin "P$1") (pinfunction "1_P$1") (pintype "passive"))
      (node (ref "T2") (pin "B") (pinfunction "B_B") (pintype "passive"))
    )
    (net (code "31") (name "Net-(R17-1)") (class "Default")
      (node (ref "Q2") (pin "B") (pinfunction "B_B") (pintype "passive"))
      (node (ref "R17") (pin "P$1") (pinfunction "1_P$1") (pintype "passive"))
    )
    (net (code "32") (name "Net-(R17-2)") (class "Default")
      (node (ref "R17") (pin "P$2") (pinfunction "2_P$2") (pintype "passive"))
      (node (ref "T2") (pin "C") (pinfunction "C_C") (pintype "passive"))
    )
    (net (code "33") (name "Net-(R19-2)") (class "Default")
      (node (ref "JP10") (pin "3") (pinfunction "3_3") (pintype "passive"))
      (node (ref "R19") (pin "P$2") (pinfunction "2_P$2") (pintype "passive"))
    )
    (net (code "34") (name "Net-(R20-2)") (class "Default")
      (node (ref "R20") (pin "P$2") (pinfunction "2_P$2") (pintype "passive"))
      (node (ref "R21") (pin "P$1") (pinfunction "1_P$1") (pintype "passive"))
      (node (ref "T3") (pin "B") (pinfunction "B_B") (pintype "passive"))
    )
    (net (code "35") (name "Net-(R22-1)") (class "Default")
      (node (ref "Q3") (pin "B") (pinfunction "B_B") (pintype "passive"))
      (node (ref "R22") (pin "P$1") (pinfunction "1_P$1") (pintype "passive"))
    )
    (net (code "36") (name "Net-(R22-2)") (class "Default")
      (node (ref "R22") (pin "P$2") (pinfunction "2_P$2") (pintype "passive"))
      (node (ref "T3") (pin "C") (pinfunction "C_C") (pintype "passive"))
    )
    (net (code "37") (name "Net-(R24-2)") (class "Default")
      (node (ref "JP11") (pin "3") (pinfunction "3_3") (pintype "passive"))
      (node (ref "R24") (pin "P$2") (pinfunction "2_P$2") (pintype "passive"))
    )
    (net (code "38") (name "Net-(R25-2)") (class "Default")
      (node (ref "R25") (pin "P$2") (pinfunction "2_P$2") (pintype "passive"))
      (node (ref "R26") (pin "P$1") (pinfunction "1_P$1") (pintype "passive"))
      (node (ref "T4") (pin "B") (pinfunction "B_B") (pintype "passive"))
    )
    (net (code "39") (name "Net-(R27-1)") (class "Default")
      (node (ref "Q4") (pin "B") (pinfunction "B_B") (pintype "passive"))
      (node (ref "R27") (pin "P$1") (pinfunction "1_P$1") (pintype "passive"))
    )
    (net (code "40") (name "Net-(R27-2)") (class "Default")
      (node (ref "R27") (pin "P$2") (pinfunction "2_P$2") (pintype "passive"))
      (node (ref "T4") (pin "C") (pinfunction "C_C") (pintype "passive"))
    )
    (net (code "41") (name "Net-(R29-2)") (class "Default")
      (node (ref "JP12") (pin "3") (pinfunction "3_3") (pintype "passive"))
      (node (ref "R29") (pin "P$2") (pinfunction "2_P$2") (pintype "passive"))
    )
    (net (code "42") (name "Net-(R30-2)") (class "Default")
      (node (ref "R30") (pin "P$2") (pinfunction "2_P$2") (pintype "passive"))
      (node (ref "R31") (pin "P$1") (pinfunction "1_P$1") (pintype "passive"))
      (node (ref "T5") (pin "B") (pinfunction "B_B") (pintype "passive"))
    )
    (net (code "43") (name "Net-(R32-1)") (class "Default")
      (node (ref "Q5") (pin "B") (pinfunction "B_B") (pintype "passive"))
      (node (ref "R32") (pin "P$1") (pinfunction "1_P$1") (pintype "passive"))
    )
    (net (code "44") (name "Net-(R32-2)") (class "Default")
      (node (ref "R32") (pin "P$2") (pinfunction "2_P$2") (pintype "passive"))
      (node (ref "T5") (pin "C") (pinfunction "C_C") (pintype "passive"))
    )
    (net (code "45") (name "Net-(R34-2)") (class "Default")
      (node (ref "JP13") (pin "3") (pinfunction "3_3") (pintype "passive"))
      (node (ref "R34") (pin "P$2") (pinfunction "2_P$2") (pintype "passive"))
    )
    (net (code "46") (name "Net-(R35-2)") (class "Default")
      (node (ref "R35") (pin "P$2") (pinfunction "2_P$2") (pintype "passive"))
      (node (ref "R36") (pin "P$1") (pinfunction "1_P$1") (pintype "passive"))
      (node (ref "T6") (pin "B") (pinfunction "B_B") (pintype "passive"))
    )
    (net (code "47") (name "Net-(R37-1)") (class "Default")
      (node (ref "Q6") (pin "B") (pinfunction "B_B") (pintype "passive"))
      (node (ref "R37") (pin "P$1") (pinfunction "1_P$1") (pintype "passive"))
    )
    (net (code "48") (name "Net-(R37-2)") (class "Default")
      (node (ref "R37") (pin "P$2") (pinfunction "2_P$2") (pintype "passive"))
      (node (ref "T6") (pin "C") (pinfunction "C_C") (pintype "passive"))
    )
    (net (code "49") (name "Net-(R39-2)") (class "Default")
      (node (ref "JP14") (pin "3") (pinfunction "3_3") (pintype "passive"))
      (node (ref "R39") (pin "P$2") (pinfunction "2_P$2") (pintype "passive"))
    )
    (net (code "50") (name "Net-(R40-2)") (class "Default")
      (node (ref "R40") (pin "P$2") (pinfunction "2_P$2") (pintype "passive"))
      (node (ref "R41") (pin "P$1") (pinfunction "1_P$1") (pintype "passive"))
      (node (ref "T7") (pin "B") (pinfunction "B_B") (pintype "passive"))
    )
    (net (code "51") (name "Net-(R42-1)") (class "Default")
      (node (ref "Q7") (pin "B") (pinfunction "B_B") (pintype "passive"))
      (node (ref "R42") (pin "P$1") (pinfunction "1_P$1") (pintype "passive"))
    )
    (net (code "52") (name "Net-(R42-2)") (class "Default")
      (node (ref "R42") (pin "P$2") (pinfunction "2_P$2") (pintype "passive"))
      (node (ref "T7") (pin "C") (pinfunction "C_C") (pintype "passive"))
    )
    (net (code "53") (name "Net-(R44-1)") (class "Default")
      (node (ref "R44") (pin "P$1") (pinfunction "1_P$1") (pintype "passive"))
      (node (ref "U1") (pin "23") (pinfunction "#OE_23") (pintype "input"))
    )
    (net (code "54") (name "Net-(R45-1)") (class "Default")
      (node (ref "JP19") (pin "3") (pinfunction "3_3") (pintype "passive"))
      (node (ref "R45") (pin "P$1") (pinfunction "1_P$1") (pintype "passive"))
    )
    (net (code "55") (name "Net-(R46-1)") (class "Default")
      (node (ref "JP18") (pin "3") (pinfunction "3_3") (pintype "passive"))
      (node (ref "R46") (pin "P$1") (pinfunction "1_P$1") (pintype "passive"))
    )
    (net (code "56") (name "Net-(R48-2)") (class "Default")
      (node (ref "R48") (pin "P$2") (pinfunction "2_P$2") (pintype "passive"))
      (node (ref "R49") (pin "P$1") (pinfunction "1_P$1") (pintype "passive"))
      (node (ref "T9") (pin "B") (pinfunction "B_B") (pintype "passive"))
    )
    (net (code "57") (name "Net-(R50-1)") (class "Default")
      (node (ref "JP16") (pin "3") (pinfunction "3_3") (pintype "passive"))
      (node (ref "R50") (pin "P$1") (pinfunction "1_P$1") (pintype "passive"))
    )
    (net (code "58") (name "Net-(R51-1)") (class "Default")
      (node (ref "JP15") (pin "3") (pinfunction "3_3") (pintype "passive"))
      (node (ref "R51") (pin "P$1") (pinfunction "1_P$1") (pintype "passive"))
    )
    (net (code "59") (name "Net-(R52-1)") (class "Default")
      (node (ref "JP5") (pin "3") (pinfunction "3_3") (pintype "passive"))
      (node (ref "R52") (pin "P$1") (pinfunction "1_P$1") (pintype "passive"))
    )
    (net (code "60") (name "Net-(R53-1)") (class "Default")
      (node (ref "Q9") (pin "B") (pinfunction "B_B") (pintype "passive"))
      (node (ref "R53") (pin "P$1") (pinfunction "1_P$1") (pintype "passive"))
    )
    (net (code "61") (name "Net-(R53-2)") (class "Default")
      (node (ref "R53") (pin "P$2") (pinfunction "2_P$2") (pintype "passive"))
      (node (ref "T9") (pin "C") (pinfunction "C_C") (pintype "passive"))
    )
    (net (code "62") (name "Net-(R54-1)") (class "Default")
      (node (ref "JP17") (pin "3") (pinfunction "3_3") (pintype "passive"))
      (node (ref "R54") (pin "P$1") (pinfunction "1_P$1") (pintype "passive"))
    )
    (net (code "63") (name "Net-(R55-1)") (class "Default")
      (node (ref "JP8") (pin "3") (pinfunction "3_3") (pintype "passive"))
      (node (ref "R55") (pin "P$1") (pinfunction "1_P$1") (pintype "passive"))
    )
    (net (code "64") (name "Net-(R56-1)") (class "Default")
      (node (ref "JP7") (pin "3") (pinfunction "3_3") (pintype "passive"))
      (node (ref "R56") (pin "P$1") (pinfunction "1_P$1") (pintype "passive"))
    )
    (net (code "65") (name "Net-(R57-1)") (class "Default")
      (node (ref "JP6") (pin "3") (pinfunction "3_3") (pintype "passive"))
      (node (ref "R57") (pin "P$1") (pinfunction "1_P$1") (pintype "passive"))
    )
    (net (code "66") (name "Net-(R58-1)") (class "Default")
      (node (ref "R58") (pin "P$1") (pinfunction "1_P$1") (pintype "passive"))
      (node (ref "U3") (pin "C") (pinfunction "C_C") (pintype "passive"))
    )
    (net (code "67") (name "Net-(R58-2)") (class "Default")
      (node (ref "LED3") (pin "C") (pinfunction "C_C") (pintype "passive"))
      (node (ref "R58") (pin "P$2") (pinfunction "2_P$2") (pintype "passive"))
    )
    (net (code "68") (name "Net-(R59-2)") (class "Default")
      (node (ref "R59") (pin "P$2") (pinfunction "2_P$2") (pintype "passive"))
      (node (ref "U3") (pin "B") (pinfunction "B_B") (pintype "passive"))
    )
    (net (code "69") (name "Net-(R60-1)") (class "Default")
      (node (ref "R60") (pin "P$1") (pinfunction "1_P$1") (pintype "passive"))
      (node (ref "U4") (pin "C") (pinfunction "C_C") (pintype "passive"))
    )
    (net (code "70") (name "Net-(R60-2)") (class "Default")
      (node (ref "LED4") (pin "C") (pinfunction "C_C") (pintype "passive"))
      (node (ref "R60") (pin "P$2") (pinfunction "2_P$2") (pintype "passive"))
    )
    (net (code "71") (name "Net-(R61-2)") (class "Default")
      (node (ref "R61") (pin "P$2") (pinfunction "2_P$2") (pintype "passive"))
      (node (ref "U4") (pin "B") (pinfunction "B_B") (pintype "passive"))
    )
    (net (code "72") (name "Net-(R62-1)") (class "Default")
      (node (ref "R62") (pin "P$1") (pinfunction "1_P$1") (pintype "passive"))
      (node (ref "U5") (pin "C") (pinfunction "C_C") (pintype "passive"))
    )
    (net (code "73") (name "Net-(R62-2)") (class "Default")
      (node (ref "LED5") (pin "C") (pinfunction "C_C") (pintype "passive"))
      (node (ref "R62") (pin "P$2") (pinfunction "2_P$2") (pintype "passive"))
    )
    (net (code "74") (name "Net-(R63-2)") (class "Default")
      (node (ref "R63") (pin "P$2") (pinfunction "2_P$2") (pintype "passive"))
      (node (ref "U5") (pin "B") (pinfunction "B_B") (pintype "passive"))
    )
    (net (code "75") (name "Net-(R64-1)") (class "Default")
      (node (ref "R64") (pin "P$1") (pinfunction "1_P$1") (pintype "passive"))
      (node (ref "U6") (pin "C") (pinfunction "C_C") (pintype "passive"))
    )
    (net (code "76") (name "Net-(R64-2)") (class "Default")
      (node (ref "LED6") (pin "C") (pinfunction "C_C") (pintype "passive"))
      (node (ref "R64") (pin "P$2") (pinfunction "2_P$2") (pintype "passive"))
    )
    (net (code "77") (name "Net-(R65-2)") (class "Default")
      (node (ref "R65") (pin "P$2") (pinfunction "2_P$2") (pintype "passive"))
      (node (ref "U6") (pin "B") (pinfunction "B_B") (pintype "passive"))
    )
    (net (code "78") (name "Net-(R66-1)") (class "Default")
      (node (ref "R66") (pin "P$1") (pinfunction "1_P$1") (pintype "passive"))
      (node (ref "U7") (pin "C") (pinfunction "C_C") (pintype "passive"))
    )
    (net (code "79") (name "Net-(R66-2)") (class "Default")
      (node (ref "LED7") (pin "C") (pinfunction "C_C") (pintype "passive"))
      (node (ref "R66") (pin "P$2") (pinfunction "2_P$2") (pintype "passive"))
    )
    (net (code "80") (name "Net-(R67-2)") (class "Default")
      (node (ref "R67") (pin "P$2") (pinfunction "2_P$2") (pintype "passive"))
      (node (ref "U7") (pin "B") (pinfunction "B_B") (pintype "passive"))
    )
    (net (code "81") (name "Net-(R68-1)") (class "Default")
      (node (ref "R68") (pin "P$1") (pinfunction "1_P$1") (pintype "passive"))
      (node (ref "U8") (pin "C") (pinfunction "C_C") (pintype "passive"))
    )
    (net (code "82") (name "Net-(R68-2)") (class "Default")
      (node (ref "LED8") (pin "C") (pinfunction "C_C") (pintype "passive"))
      (node (ref "R68") (pin "P$2") (pinfunction "2_P$2") (pintype "passive"))
    )
    (net (code "83") (name "Net-(R69-2)") (class "Default")
      (node (ref "R69") (pin "P$2") (pinfunction "2_P$2") (pintype "passive"))
      (node (ref "U8") (pin "B") (pinfunction "B_B") (pintype "passive"))
    )
    (net (code "84") (name "Net-(R70-1)") (class "Default")
      (node (ref "R70") (pin "P$1") (pinfunction "1_P$1") (pintype "passive"))
      (node (ref "U9") (pin "C") (pinfunction "C_C") (pintype "passive"))
    )
    (net (code "85") (name "Net-(R70-2)") (class "Default")
      (node (ref "LED9") (pin "C") (pinfunction "C_C") (pintype "passive"))
      (node (ref "R70") (pin "P$2") (pinfunction "2_P$2") (pintype "passive"))
    )
    (net (code "86") (name "Net-(R71-2)") (class "Default")
      (node (ref "R71") (pin "P$2") (pinfunction "2_P$2") (pintype "passive"))
      (node (ref "U9") (pin "B") (pinfunction "B_B") (pintype "passive"))
    )
    (net (code "87") (name "Net-(R72-1)") (class "Default")
      (node (ref "R72") (pin "P$1") (pinfunction "1_P$1") (pintype "passive"))
      (node (ref "U10") (pin "C") (pinfunction "C_C") (pintype "passive"))
    )
    (net (code "88") (name "Net-(R72-2)") (class "Default")
      (node (ref "LED10") (pin "C") (pinfunction "C_C") (pintype "passive"))
      (node (ref "R72") (pin "P$2") (pinfunction "2_P$2") (pintype "passive"))
    )
    (net (code "89") (name "Net-(R73-2)") (class "Default")
      (node (ref "R73") (pin "P$2") (pinfunction "2_P$2") (pintype "passive"))
      (node (ref "U10") (pin "B") (pinfunction "B_B") (pintype "passive"))
    )
    (net (code "90") (name "Net-(U2-VIN)") (class "Default")
      (node (ref "C17") (pin "2") (pinfunction "2_2") (pintype "passive"))
      (node (ref "CN1") (pin "PWR") (pinfunction "PWR_PWR") (pintype "power_in"))
      (node (ref "U2") (pin "1") (pinfunction "VIN_1") (pintype "power_in"))
    )
    (net (code "91") (name "PWM_0") (class "Default")
      (node (ref "R39") (pin "P$1") (pinfunction "1_P$1") (pintype "passive"))
      (node (ref "U1") (pin "13") (pinfunction "PWM7_13") (pintype "output"))
    )
    (net (code "92") (name "PWM_1") (class "Default")
      (node (ref "R34") (pin "P$1") (pinfunction "1_P$1") (pintype "passive"))
      (node (ref "U1") (pin "12") (pinfunction "PWM6_12") (pintype "output"))
    )
    (net (code "93") (name "PWM_2") (class "Default")
      (node (ref "R29") (pin "P$1") (pinfunction "1_P$1") (pintype "passive"))
      (node (ref "U1") (pin "11") (pinfunction "PWM5_11") (pintype "output"))
    )
    (net (code "94") (name "PWM_3") (class "Default")
      (node (ref "R24") (pin "P$1") (pinfunction "1_P$1") (pintype "passive"))
      (node (ref "U1") (pin "10") (pinfunction "PWM4_10") (pintype "output"))
    )
    (net (code "95") (name "PWM_4") (class "Default")
      (node (ref "R19") (pin "P$1") (pinfunction "1_P$1") (pintype "passive"))
      (node (ref "U1") (pin "9") (pinfunction "PWM3_9") (pintype "output"))
    )
    (net (code "96") (name "PWM_5") (class "Default")
      (node (ref "R14") (pin "P$1") (pinfunction "1_P$1") (pintype "passive"))
      (node (ref "U1") (pin "8") (pinfunction "PWM2_8") (pintype "output"))
    )
    (net (code "97") (name "PWM_6") (class "Default")
      (node (ref "R2") (pin "P$1") (pinfunction "1_P$1") (pintype "passive"))
      (node (ref "U1") (pin "7") (pinfunction "PWM1_7") (pintype "output"))
    )
    (net (code "98") (name "PWM_7") (class "Default")
      (node (ref "R1") (pin "P$1") (pinfunction "1_P$1") (pintype "passive"))
      (node (ref "U1") (pin "6") (pinfunction "PWM0_6") (pintype "output"))
    )
    (net (code "99") (name "SCL") (class "Default")
      (node (ref "IC3") (pin "1") (pinfunction "SCL_1") (pintype "bidirectional"))
      (node (ref "JP20") (pin "1") (pinfunction "1_1") (pintype "passive"))
      (node (ref "R9") (pin "P$1") (pinfunction "1_P$1") (pintype "passive"))
      (node (ref "U1") (pin "26") (pinfunction "SCL_26") (pintype "bidirectional"))
    )
    (net (code "100") (name "SDA") (class "Default")
      (node (ref "IC3") (pin "2") (pinfunction "SDA_2") (pintype "bidirectional"))
      (node (ref "JP20") (pin "2") (pinfunction "2_2") (pintype "passive"))
      (node (ref "R8") (pin "P$1") (pinfunction "1_P$1") (pintype "passive"))
      (node (ref "U1") (pin "27") (pinfunction "SDA_27") (pintype "bidirectional"))
    )
    (net (code "101") (name "SERVO_0") (class "Default")
      (node (ref "IC3") (pin "10") (pinfunction "GP0_10") (pintype "bidirectional"))
      (node (ref "R48") (pin "P$1") (pinfunction "1_P$1") (pintype "passive"))
      (node (ref "R59") (pin "P$1") (pinfunction "1_P$1") (pintype "passive"))
    )
    (net (code "102") (name "SERVO_1") (class "Default")
      (node (ref "IC3") (pin "11") (pinfunction "GP1_11") (pintype "bidirectional"))
      (node (ref "R3") (pin "P$1") (pinfunction "1_P$1") (pintype "passive"))
      (node (ref "R67") (pin "P$1") (pinfunction "1_P$1") (pintype "passive"))
    )
    (net (code "103") (name "SERVO_2") (class "Default")
      (node (ref "IC3") (pin "12") (pinfunction "GP2_12") (pintype "bidirectional"))
      (node (ref "R15") (pin "P$1") (pinfunction "1_P$1") (pintype "passive"))
      (node (ref "R61") (pin "P$1") (pinfunction "1_P$1") (pintype "passive"))
    )
    (net (code "104") (name "SERVO_3") (class "Default")
      (node (ref "IC3") (pin "13") (pinfunction "GP3_13") (pintype "bidirectional"))
      (node (ref "R20") (pin "P$1") (pinfunction "1_P$1") (pintype "passive"))
      (node (ref "R69") (pin "P$1") (pinfunction "1_P$1") (pintype "passive"))
    )
    (net (code "105") (name "SERVO_4") (class "Default")
      (node (ref "IC3") (pin "14") (pinfunction "GP4_14") (pintype "bidirectional"))
      (node (ref "R25") (pin "P$1") (pinfunction "1_P$1") (pintype "passive"))
      (node (ref "R63") (pin "P$1") (pinfunction "1_P$1") (pintype "passive"))
    )
    (net (code "106") (name "SERVO_5") (class "Default")
      (node (ref "IC3") (pin "15") (pinfunction "GP5_15") (pintype "bidirectional"))
      (node (ref "R30") (pin "P$1") (pinfunction "1_P$1") (pintype "passive"))
      (node (ref "R71") (pin "P$1") (pinfunction "1_P$1") (pintype "passive"))
    )
    (net (code "107") (name "SERVO_6") (class "Default")
      (node (ref "IC3") (pin "16") (pinfunction "GP6_16") (pintype "bidirectional"))
      (node (ref "R35") (pin "P$1") (pinfunction "1_P$1") (pintype "passive"))
      (node (ref "R65") (pin "P$1") (pinfunction "1_P$1") (pintype "passive"))
    )
    (net (code "108") (name "SERVO_7") (class "Default")
      (node (ref "IC3") (pin "17") (pinfunction "GP7_17") (pintype "bidirectional"))
      (node (ref "R40") (pin "P$1") (pinfunction "1_P$1") (pintype "passive"))
      (node (ref "R73") (pin "P$1") (pinfunction "1_P$1") (pintype "passive"))
    )
    (net (code "109") (name "VCC") (class "Default")
      (node (ref "C11") (pin "2") (pinfunction "2_2") (pintype "passive"))
      (node (ref "C12") (pin "1") (pinfunction "1_1") (pintype "passive"))
      (node (ref "C3") (pin "1") (pinfunction "+_1") (pintype "passive"))
      (node (ref "IC3") (pin "18") (pinfunction "VCC_18") (pintype "power_in"))
      (node (ref "JP1") (pin "2") (pinfunction "2_2") (pintype "passive"))
      (node (ref "LED10") (pin "A") (pinfunction "A_A") (pintype "passive"))
      (node (ref "LED3") (pin "A") (pinfunction "A_A") (pintype "passive"))
      (node (ref "LED4") (pin "A") (pinfunction "A_A") (pintype "passive"))
      (node (ref "LED5") (pin "A") (pinfunction "A_A") (pintype "passive"))
      (node (ref "LED6") (pin "A") (pinfunction "A_A") (pintype "passive"))
      (node (ref "LED7") (pin "A") (pinfunction "A_A") (pintype "passive"))
      (node (ref "LED8") (pin "A") (pinfunction "A_A") (pintype "passive"))
      (node (ref "LED9") (pin "A") (pinfunction "A_A") (pintype "passive"))
      (node (ref "Q1") (pin "E") (pinfunction "E_E") (pintype "passive"))
      (node (ref "Q2") (pin "E") (pinfunction "E_E") (pintype "passive"))
      (node (ref "Q3") (pin "E") (pinfunction "E_E") (pintype "passive"))
      (node (ref "Q4") (pin "E") (pinfunction "E_E") (pintype "passive"))
      (node (ref "Q5") (pin "E") (pinfunction "E_E") (pintype "passive"))
      (node (ref "Q6") (pin "E") (pinfunction "E_E") (pintype "passive"))
      (node (ref "Q7") (pin "E") (pinfunction "E_E") (pintype "passive"))
      (node (ref "Q9") (pin "E") (pinfunction "E_E") (pintype "passive"))
      (node (ref "R45") (pin "P$2") (pinfunction "2_P$2") (pintype "passive"))
      (node (ref "R46") (pin "P$2") (pinfunction "2_P$2") (pintype "passive"))
      (node (ref "R47") (pin "P$2") (pinfunction "2_P$2") (pintype "passive"))
      (node (ref "R50") (pin "P$2") (pinfunction "2_P$2") (pintype "passive"))
      (node (ref "R51") (pin "P$2") (pinfunction "2_P$2") (pintype "passive"))
      (node (ref "R52") (pin "P$2") (pinfunction "2_P$2") (pintype "passive"))
      (node (ref "R54") (pin "P$2") (pinfunction "2_P$2") (pintype "passive"))
      (node (ref "R55") (pin "P$2") (pinfunction "2_P$2") (pintype "passive"))
      (node (ref "R56") (pin "P$2") (pinfunction "2_P$2") (pintype "passive"))
      (node (ref "R57") (pin "P$2") (pinfunction "2_P$2") (pintype "passive"))
      (node (ref "R8") (pin "P$2") (pinfunction "2_P$2") (pintype "passive"))
      (node (ref "R9") (pin "P$2") (pinfunction "2_P$2") (pintype "passive"))
      (node (ref "U1") (pin "28") (pinfunction "VDD_28") (pintype "power_in"))
    )
    (net (code "110") (name "unconnected-(IC3-INT-Pad8)") (class "Default")
      (node (ref "IC3") (pin "8") (pinfunction "INT_8") (pintype "output"))
    )
    (net (code "111") (name "unconnected-(U1-PWM8-Pad15)") (class "Default")
      (node (ref "U1") (pin "15") (pinfunction "PWM8_15") (pintype "output"))
    )
    (net (code "112") (name "unconnected-(U1-PWM9-Pad16)") (class "Default")
      (node (ref "U1") (pin "16") (pinfunction "PWM9_16") (pintype "output"))
    )
    (net (code "113") (name "unconnected-(U1-PWM10-Pad17)") (class "Default")
      (node (ref "U1") (pin "17") (pinfunction "PWM10_17") (pintype "output"))
    )
    (net (code "114") (name "unconnected-(U1-PWM11-Pad18)") (class "Default")
      (node (ref "U1") (pin "18") (pinfunction "PWM11_18") (pintype "output"))
    )
    (net (code "115") (name "unconnected-(U1-PWM12-Pad19)") (class "Default")
      (node (ref "U1") (pin "19") (pinfunction "PWM12_19") (pintype "output"))
    )
    (net (code "116") (name "unconnected-(U1-PWM13-Pad20)") (class "Default")
      (node (ref "U1") (pin "20") (pinfunction "PWM13_20") (pintype "output"))
    )
    (net (code "117") (name "unconnected-(U1-PWM14-Pad21)") (class "Default")
      (node (ref "U1") (pin "21") (pinfunction "PWM14_21") (pintype "output"))
    )
    (net (code "118") (name "unconnected-(U1-PWM15-Pad22)") (class "Default")
      (node (ref "U1") (pin "22") (pinfunction "PWM15_22") (pintype "output"))
    )
  )
)
